# power_board1_v2_0.net
KiCad netlist of a schematic drawn in EAGLE
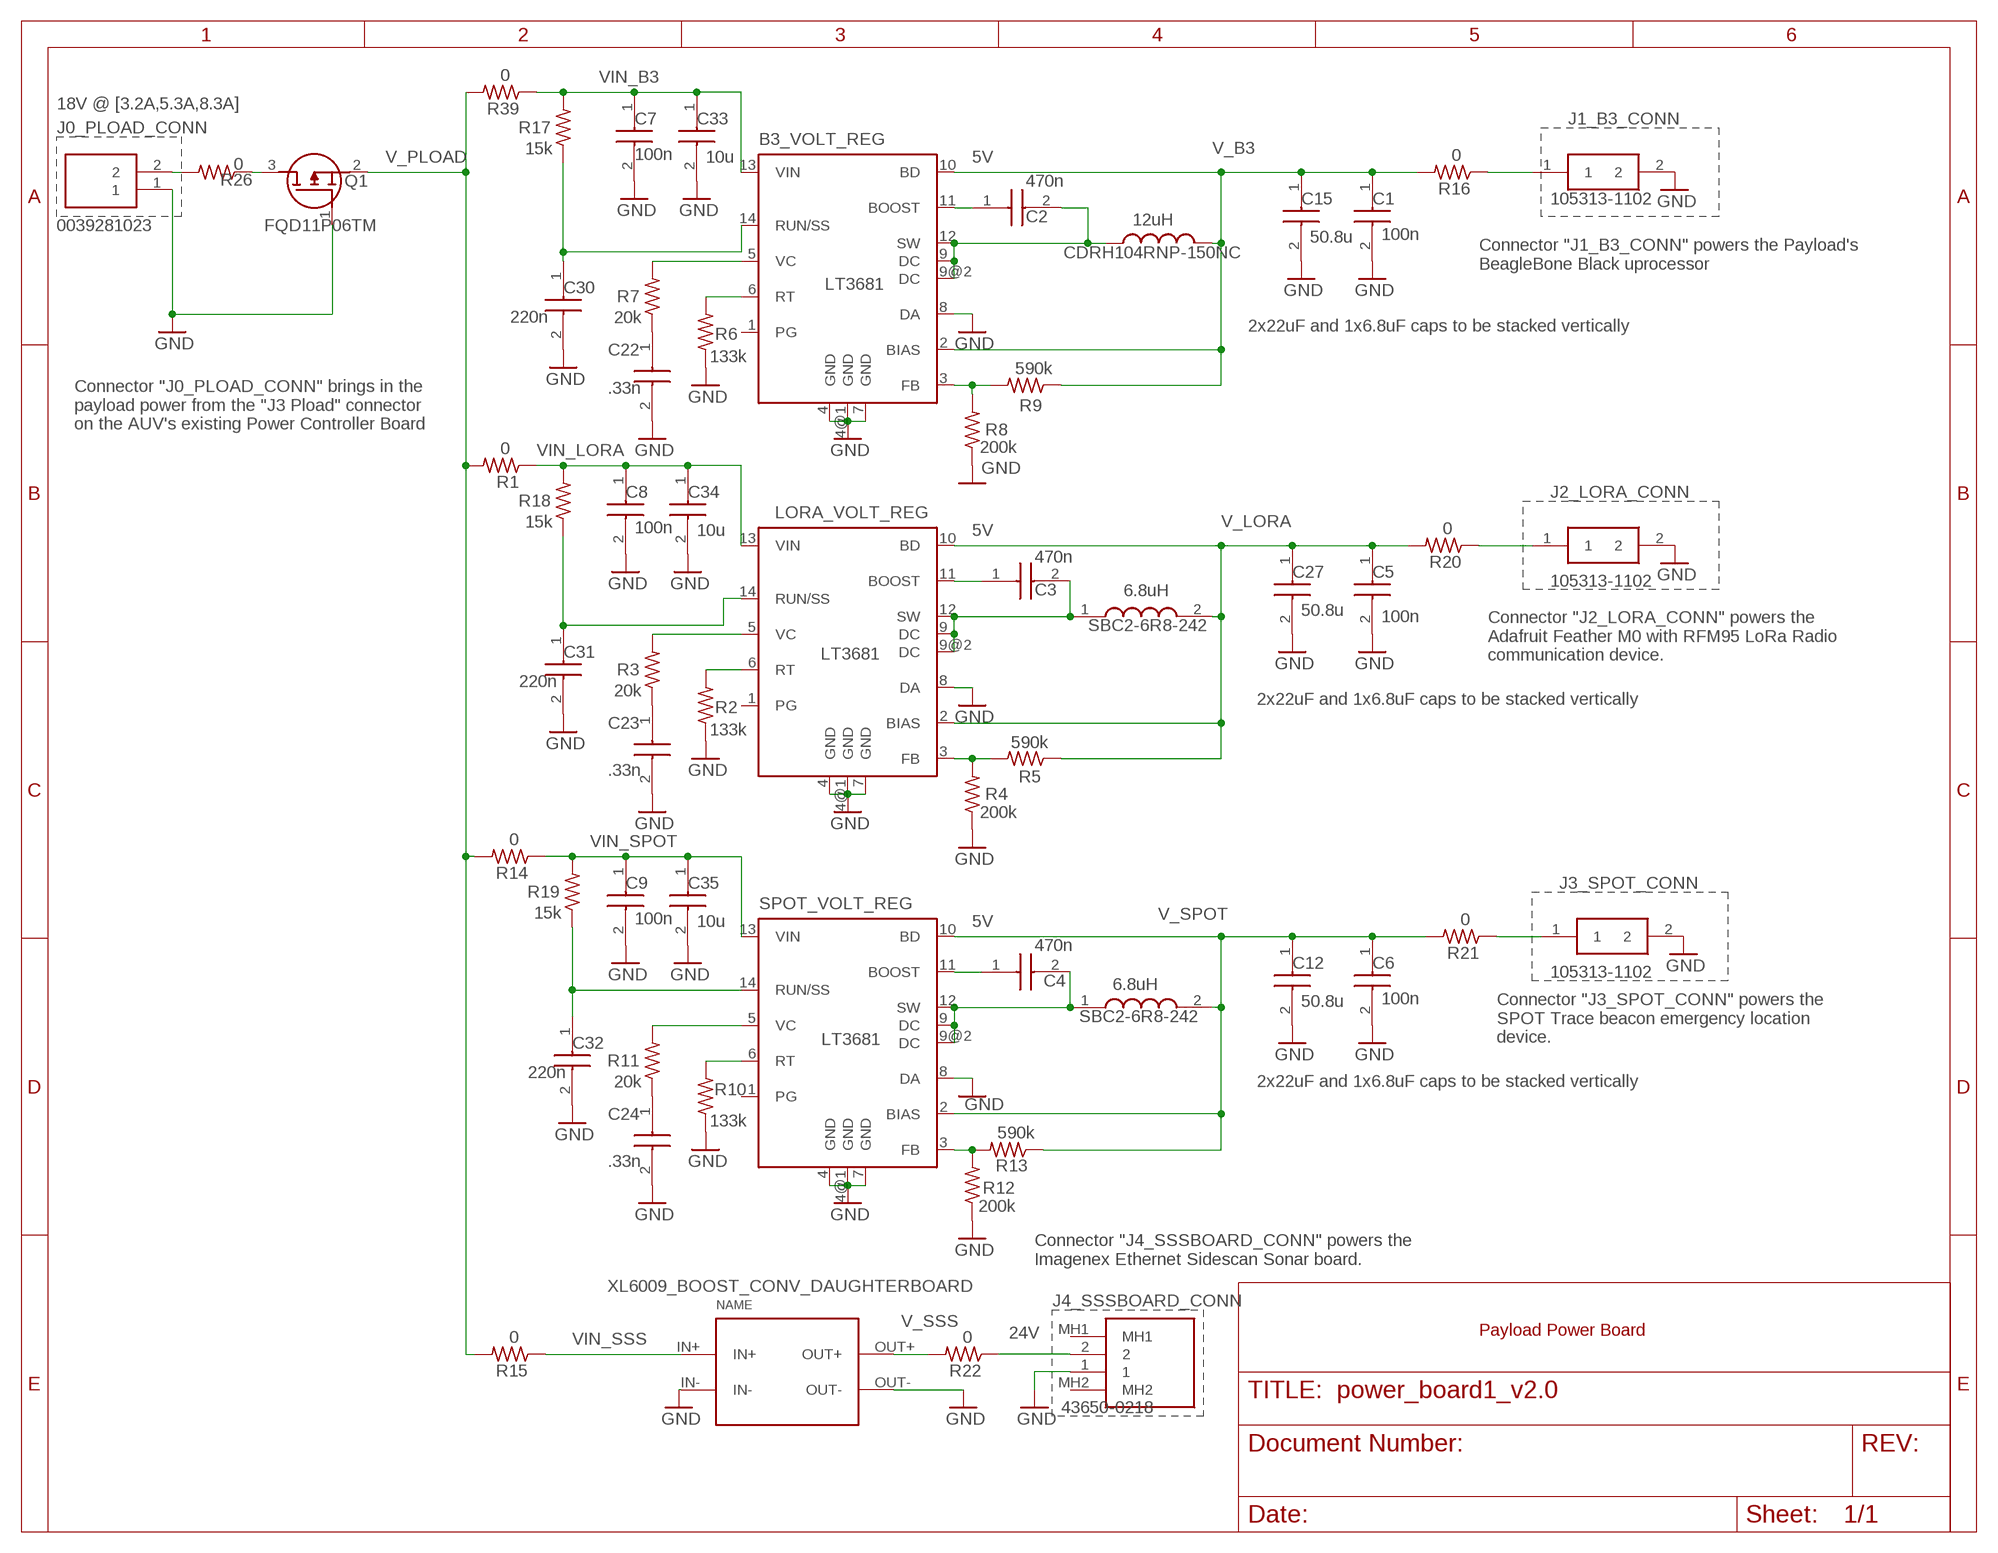
[diagram p0: schematic, sheet 1]

(export (version "E")
  (design (tool "Eeschema 10.0.6"))
  (components
    (comp (ref "B3_VOLT_REG")
      (value "LT3681")
      (footprint "eagle-import:DFN14-4X3DE")
      (fields (field (name "MPN") "LT3681EDE#PBF"))
      (libsource (lib "eagle-import") (part "LT3681"))
    )
    (comp (ref "C1")
      (value "100n")
      (footprint "eagle-import:CAPC1608X90N")
      (fields
        (field (name "MANUFACTURER_PART_NUMBER") "06033C104KAT4A")
        (field (name "MOUSER_PART_NUMBER") "581-06033C104KAT4A")
      )
      (libsource (lib "eagle-import") (part "06033C104KAT4A"))
    )
    (comp (ref "C2")
      (value "470n")
      (footprint "eagle-import:CAPC1608X90N")
      (fields
        (field (name "MANUFACTURER_PART_NUMBER") "06033C474JAT2A")
        (field (name "MOUSER_PART_NUMBER") "581-06033C474JAT2A")
      )
      (libsource (lib "eagle-import") (part "06033C474JAT2A"))
    )
    (comp (ref "C3")
      (value "470n")
      (footprint "eagle-import:CAPC1608X90N")
      (fields
        (field (name "MANUFACTURER_PART_NUMBER") "06033C474JAT2A")
        (field (name "MOUSER_PART_NUMBER") "581-06033C474JAT2A")
      )
      (libsource (lib "eagle-import") (part "06033C474JAT2A"))
    )
    (comp (ref "C4")
      (value "470n")
      (footprint "eagle-import:CAPC1608X90N")
      (fields
        (field (name "MANUFACTURER_PART_NUMBER") "06033C474JAT2A")
        (field (name "MOUSER_PART_NUMBER") "581-06033C474JAT2A")
      )
      (libsource (lib "eagle-import") (part "06033C474JAT2A"))
    )
    (comp (ref "C5")
      (value "100n")
      (footprint "eagle-import:CAPC1608X90N")
      (fields
        (field (name "MANUFACTURER_PART_NUMBER") "06033C104KAT4A")
        (field (name "MOUSER_PART_NUMBER") "581-06033C104KAT4A")
      )
      (libsource (lib "eagle-import") (part "06033C104KAT4A"))
    )
    (comp (ref "C6")
      (value "100n")
      (footprint "eagle-import:CAPC1608X90N")
      (fields
        (field (name "MANUFACTURER_PART_NUMBER") "06033C104KAT4A")
        (field (name "MOUSER_PART_NUMBER") "581-06033C104KAT4A")
      )
      (libsource (lib "eagle-import") (part "06033C104KAT4A"))
    )
    (comp (ref "C7")
      (value "100n")
      (footprint "eagle-import:CAPC1608X90N")
      (fields
        (field (name "MANUFACTURER_PART_NUMBER") "06031C104KAT2A")
        (field (name "MOUSER_PART_NUMBER") "581-06031C104KAT2A")
      )
      (libsource (lib "eagle-import") (part "06031C104KAT2A"))
    )
    (comp (ref "C8")
      (value "100n")
      (footprint "eagle-import:CAPC1608X90N")
      (fields
        (field (name "MANUFACTURER_PART_NUMBER") "06031C104KAT2A")
        (field (name "MOUSER_PART_NUMBER") "581-06031C104KAT2A")
      )
      (libsource (lib "eagle-import") (part "06031C104KAT2A"))
    )
    (comp (ref "C9")
      (value "100n")
      (footprint "eagle-import:CAPC1608X90N")
      (fields
        (field (name "MANUFACTURER_PART_NUMBER") "06031C104KAT2A")
        (field (name "MOUSER_PART_NUMBER") "581-06031C104KAT2A")
      )
      (libsource (lib "eagle-import") (part "06031C104KAT2A"))
    )
    (comp (ref "C12")
      (value "50.8u")
      (footprint "eagle-import:CAPC3225X279N")
      (fields
        (field (name "MANUFACTURER_PART_NUMBER") "12103C226KAT2A")
        (field (name "MOUSER_PART_NUMBER") "581-12103C226KAT2A")
      )
      (libsource (lib "eagle-import") (part "12103C226KAT2A"))
    )
    (comp (ref "C15")
      (value "50.8u")
      (footprint "eagle-import:CAPC3225X279N")
      (fields
        (field (name "MANUFACTURER_PART_NUMBER") "12103C226KAT2A")
        (field (name "MOUSER_PART_NUMBER") "581-12103C226KAT2A")
      )
      (libsource (lib "eagle-import") (part "12103C226KAT2A"))
    )
    (comp (ref "C22")
      (value ".33n")
      (footprint "eagle-import:CAPC2012X140N")
      (fields
        (field (name "MANUFACTURER_PART_NUMBER") "08053C334KAT2A")
        (field (name "MOUSER_PART_NUMBER") "581-08053C334KAT2A")
        (field (name "RS_PART_NUMBER") "1747387")
      )
      (libsource (lib "eagle-import") (part "08053C334KAT2A"))
    )
    (comp (ref "C23")
      (value ".33n")
      (footprint "eagle-import:CAPC2012X140N")
      (fields
        (field (name "MANUFACTURER_PART_NUMBER") "08053C334KAT2A")
        (field (name "MOUSER_PART_NUMBER") "581-08053C334KAT2A")
        (field (name "RS_PART_NUMBER") "1747387")
      )
      (libsource (lib "eagle-import") (part "08053C334KAT2A"))
    )
    (comp (ref "C24")
      (value ".33n")
      (footprint "eagle-import:CAPC2012X140N")
      (fields
        (field (name "MANUFACTURER_PART_NUMBER") "08053C334KAT2A")
        (field (name "MOUSER_PART_NUMBER") "581-08053C334KAT2A")
        (field (name "RS_PART_NUMBER") "1747387")
      )
      (libsource (lib "eagle-import") (part "08053C334KAT2A"))
    )
    (comp (ref "C27")
      (value "50.8u")
      (footprint "eagle-import:CAPC3225X279N")
      (fields
        (field (name "MANUFACTURER_PART_NUMBER") "12103C226KAT2A")
        (field (name "MOUSER_PART_NUMBER") "581-12103C226KAT2A")
      )
      (libsource (lib "eagle-import") (part "12103C226KAT2A"))
    )
    (comp (ref "C30")
      (value "220n")
      (footprint "eagle-import:CAPC2012X140N")
      (fields
        (field (name "MANUFACTURER_PART_NUMBER") "08051C224KAT2A")
        (field (name "MOUSER_PART_NUMBER") "581-08051C224KAT2A")
      )
      (libsource (lib "eagle-import") (part "08051C224KAT2A"))
    )
    (comp (ref "C31")
      (value "220n")
      (footprint "eagle-import:CAPC2012X140N")
      (fields
        (field (name "MANUFACTURER_PART_NUMBER") "08051C224KAT2A")
        (field (name "MOUSER_PART_NUMBER") "581-08051C224KAT2A")
      )
      (libsource (lib "eagle-import") (part "08051C224KAT2A"))
    )
    (comp (ref "C32")
      (value "220n")
      (footprint "eagle-import:CAPC2012X140N")
      (fields
        (field (name "MANUFACTURER_PART_NUMBER") "08051C224KAT2A")
        (field (name "MOUSER_PART_NUMBER") "581-08051C224KAT2A")
      )
      (libsource (lib "eagle-import") (part "08051C224KAT2A"))
    )
    (comp (ref "C33")
      (value "10u")
      (footprint "eagle-import:CAPC5750X279N")
      (fields
        (field (name "MANUFACTURER_PART_NUMBER") "22201C106KAT2A")
        (field (name "MOUSER_PART_NUMBER") "581-22201C106KAT2A")
      )
      (libsource (lib "eagle-import") (part "22201C106KAT2A"))
    )
    (comp (ref "C34")
      (value "10u")
      (footprint "eagle-import:CAPC5750X279N")
      (fields
        (field (name "MANUFACTURER_PART_NUMBER") "22201C106KAT2A")
        (field (name "MOUSER_PART_NUMBER") "581-22201C106KAT2A")
      )
      (libsource (lib "eagle-import") (part "22201C106KAT2A"))
    )
    (comp (ref "C35")
      (value "10u")
      (footprint "eagle-import:CAPC5750X279N")
      (fields
        (field (name "MANUFACTURER_PART_NUMBER") "22201C106KAT2A")
        (field (name "MOUSER_PART_NUMBER") "581-22201C106KAT2A")
      )
      (libsource (lib "eagle-import") (part "22201C106KAT2A"))
    )
    (comp (ref "INDUCTOR_3")
      (value "CDRH104RNP-150NC")
      (footprint "eagle-import:INDPM102100X400N")
      (fields (field (name "MOUSER_PART_NUMBER") "851-CDRH104RNP-150NC"))
      (libsource (lib "eagle-import") (part "CDRH104RNP-150NC"))
    )
    (comp (ref "J0_PLOAD_CONN")
      (value "0039281023")
      (footprint "eagle-import:SHDR2W145P0X550_1X2_960X540X13")
      (libsource (lib "eagle-import") (part "0039281023"))
    )
    (comp (ref "J1_B3_CONN")
      (value "105313-1102")
      (footprint "eagle-import:1053131102")
      (fields (field (name "MOUSER_PART_NUMBER") "538-105313-1102") (field (name "RS_PART_NUMBER") "1623686"))
      (libsource (lib "eagle-import") (part "105313-1102"))
    )
    (comp (ref "J2_LORA_CONN")
      (value "105313-1102")
      (footprint "eagle-import:1053131102")
      (fields (field (name "MOUSER_PART_NUMBER") "538-105313-1102") (field (name "RS_PART_NUMBER") "1623686"))
      (libsource (lib "eagle-import") (part "105313-1102"))
    )
    (comp (ref "J3_SPOT_CONN")
      (value "105313-1102")
      (footprint "eagle-import:1053131102")
      (fields (field (name "MOUSER_PART_NUMBER") "538-105313-1102") (field (name "RS_PART_NUMBER") "1623686"))
      (libsource (lib "eagle-import") (part "105313-1102"))
    )
    (comp (ref "J4_SSSBOARD_CONN")
      (value "43650-0218")
      (footprint "eagle-import:436500218")
      (fields (field (name "MOUSER_PART_NUMBER") "538-43650-0218") (field (name "RS_PART_NUMBER") "6704705P"))
      (libsource (lib "eagle-import") (part "43650-0218"))
    )
    (comp (ref "L4")
      (value "SBC2-6R8-242")
      (footprint "eagle-import:SBC26R8242")
      (fields (field (name "MOUSER_PART_NUMBER") "80-SBC2-6R8-242"))
      (libsource (lib "eagle-import") (part "SBC2-6R8-242"))
    )
    (comp (ref "L5")
      (value "SBC2-6R8-242")
      (footprint "eagle-import:SBC26R8242")
      (fields (field (name "MOUSER_PART_NUMBER") "80-SBC2-6R8-242"))
      (libsource (lib "eagle-import") (part "SBC2-6R8-242"))
    )
    (comp (ref "LORA_VOLT_REG")
      (value "LT3681")
      (footprint "eagle-import:DFN14-4X3DE")
      (fields (field (name "MPN") "LT3681EDE#PBF"))
      (libsource (lib "eagle-import") (part "LT3681"))
    )
    (comp (ref "Q1")
      (value "FQD11P06TM")
      (footprint "eagle-import:DPAK3-CASE-369AS")
      (fields (field (name "MOUSER_PART_NUMBER") "512-FQD11P06TM") (field (name "RS_PART_NUMBER") "6710949P"))
      (libsource (lib "eagle-import") (part "FQD11P06TM"))
    )
    (comp (ref "R1")
      (value "0")
      (footprint "eagle-import:0207_2V")
      (fields (field (name "MFR") "Yageo") (field (name "MPN") "RC0805FR-0710KL"))
      (libsource (lib "eagle-import") (part "R-US_0207/2V"))
    )
    (comp (ref "R2")
      (value "133k")
      (footprint "eagle-import:R0603")
      (libsource (lib "eagle-import") (part "R-US_R0603"))
    )
    (comp (ref "R3")
      (value "20k")
      (footprint "eagle-import:R0603")
      (libsource (lib "eagle-import") (part "R-US_R0603"))
    )
    (comp (ref "R4")
      (value "200k")
      (footprint "eagle-import:R0603")
      (libsource (lib "eagle-import") (part "R-US_R0603"))
    )
    (comp (ref "R5")
      (value "590k")
      (footprint "eagle-import:R0603")
      (libsource (lib "eagle-import") (part "R-US_R0603"))
    )
    (comp (ref "R6")
      (value "133k")
      (footprint "eagle-import:R0603")
      (libsource (lib "eagle-import") (part "R-US_R0603"))
    )
    (comp (ref "R7")
      (value "20k")
      (footprint "eagle-import:R0603")
      (libsource (lib "eagle-import") (part "R-US_R0603"))
    )
    (comp (ref "R8")
      (value "200k")
      (footprint "eagle-import:R0603")
      (libsource (lib "eagle-import") (part "R-US_R0603"))
    )
    (comp (ref "R9")
      (value "590k")
      (footprint "eagle-import:R0603")
      (libsource (lib "eagle-import") (part "R-US_R0603"))
    )
    (comp (ref "R10")
      (value "133k")
      (footprint "eagle-import:R0603")
      (libsource (lib "eagle-import") (part "R-US_R0603"))
    )
    (comp (ref "R11")
      (value "20k")
      (footprint "eagle-import:R0603")
      (libsource (lib "eagle-import") (part "R-US_R0603"))
    )
    (comp (ref "R12")
      (value "200k")
      (footprint "eagle-import:R0603")
      (libsource (lib "eagle-import") (part "R-US_R0603"))
    )
    (comp (ref "R13")
      (value "590k")
      (footprint "eagle-import:R0603")
      (libsource (lib "eagle-import") (part "R-US_R0603"))
    )
    (comp (ref "R14")
      (value "0")
      (footprint "eagle-import:0207_2V")
      (fields (field (name "MFR") "Yageo") (field (name "MPN") "RC0805FR-0710KL"))
      (libsource (lib "eagle-import") (part "R-US_0207/2V"))
    )
    (comp (ref "R15")
      (value "0")
      (footprint "eagle-import:0207_2V")
      (fields (field (name "MFR") "Yageo") (field (name "MPN") "RC0805FR-0710KL"))
      (libsource (lib "eagle-import") (part "R-US_0207/2V"))
    )
    (comp (ref "R16")
      (value "0")
      (footprint "eagle-import:0207_2V")
      (fields (field (name "MFR") "Yageo") (field (name "MPN") "RC0805FR-0710KL"))
      (libsource (lib "eagle-import") (part "R-US_0207/2V"))
    )
    (comp (ref "R17")
      (value "15k")
      (footprint "eagle-import:R0603")
      (libsource (lib "eagle-import") (part "R-US_R0603"))
    )
    (comp (ref "R18")
      (value "15k")
      (footprint "eagle-import:R0603")
      (libsource (lib "eagle-import") (part "R-US_R0603"))
    )
    (comp (ref "R19")
      (value "15k")
      (footprint "eagle-import:R0603")
      (libsource (lib "eagle-import") (part "R-US_R0603"))
    )
    (comp (ref "R20")
      (value "0")
      (footprint "eagle-import:0207_2V")
      (fields (field (name "MFR") "Yageo") (field (name "MPN") "RC0805FR-0710KL"))
      (libsource (lib "eagle-import") (part "R-US_0207/2V"))
    )
    (comp (ref "R21")
      (value "0")
      (footprint "eagle-import:0207_2V")
      (fields (field (name "MFR") "Yageo") (field (name "MPN") "RC0805FR-0710KL"))
      (libsource (lib "eagle-import") (part "R-US_0207/2V"))
    )
    (comp (ref "R22")
      (value "0")
      (footprint "eagle-import:0207_2V")
      (fields (field (name "MFR") "Yageo") (field (name "MPN") "RC0805FR-0710KL"))
      (libsource (lib "eagle-import") (part "R-US_0207/2V"))
    )
    (comp (ref "R26")
      (value "0")
      (footprint "eagle-import:0207_2V")
      (fields (field (name "MFR") "Yageo") (field (name "MPN") "RC0805FR-0710KL"))
      (libsource (lib "eagle-import") (part "R-US_0207/2V"))
    )
    (comp (ref "R39")
      (value "0")
      (footprint "eagle-import:0207_2V")
      (fields (field (name "MFR") "Yageo") (field (name "MPN") "RC0805FR-0710KL"))
      (libsource (lib "eagle-import") (part "R-US_0207/2V"))
    )
    (comp (ref "SPOT_VOLT_REG")
      (value "LT3681")
      (footprint "eagle-import:DFN14-4X3DE")
      (fields (field (name "MPN") "LT3681EDE#PBF"))
      (libsource (lib "eagle-import") (part "LT3681"))
    )
    (comp (ref "XL6009_BOOST_CONV_DAUGHTERBOARD")
      (value "XL6009")
      (footprint "eagle-import:CP8-ADJ")
      (libsource (lib "eagle-import") (part "CP8-ADJ"))
    )
  )
  (nets
    (net (code "1") (name "/VIN_B3") (class "Default")
      (node (ref "B3_VOLT_REG") (pin "13") (pinfunction "VIN_13") (pintype "input"))
      (node (ref "C33") (pin "1") (pinfunction "1_1") (pintype "bidirectional"))
      (node (ref "C7") (pin "1") (pinfunction "1_1") (pintype "bidirectional"))
      (node (ref "R17") (pin "2") (pinfunction "2_2") (pintype "passive"))
      (node (ref "R39") (pin "1") (pinfunction "1_1") (pintype "passive"))
    )
    (net (code "2") (name "/VIN_LORA") (class "Default")
      (node (ref "C34") (pin "1") (pinfunction "1_1") (pintype "bidirectional"))
      (node (ref "C8") (pin "1") (pinfunction "1_1") (pintype "bidirectional"))
      (node (ref "LORA_VOLT_REG") (pin "13") (pinfunction "VIN_13") (pintype "input"))
      (node (ref "R1") (pin "1") (pinfunction "1_1") (pintype "passive"))
      (node (ref "R18") (pin "2") (pinfunction "2_2") (pintype "passive"))
    )
    (net (code "3") (name "/VIN_SPOT") (class "Default")
      (node (ref "C35") (pin "1") (pinfunction "1_1") (pintype "bidirectional"))
      (node (ref "C9") (pin "1") (pinfunction "1_1") (pintype "bidirectional"))
      (node (ref "R14") (pin "1") (pinfunction "1_1") (pintype "passive"))
      (node (ref "R19") (pin "2") (pinfunction "2_2") (pintype "passive"))
      (node (ref "SPOT_VOLT_REG") (pin "13") (pinfunction "VIN_13") (pintype "input"))
    )
    (net (code "4") (name "/VIN_SSS") (class "Default")
      (node (ref "R15") (pin "1") (pinfunction "1_1") (pintype "passive"))
      (node (ref "XL6009_BOOST_CONV_DAUGHTERBOARD") (pin "IN+") (pinfunction "IN+_IN+") (pintype "passive"))
    )
    (net (code "5") (name "/V_B3") (class "Default")
      (node (ref "B3_VOLT_REG") (pin "10") (pinfunction "BD_10") (pintype "input"))
      (node (ref "B3_VOLT_REG") (pin "2") (pinfunction "BIAS_2") (pintype "input"))
      (node (ref "C1") (pin "1") (pinfunction "1_1") (pintype "bidirectional"))
      (node (ref "C15") (pin "1") (pinfunction "1_1") (pintype "bidirectional"))
      (node (ref "INDUCTOR_3") (pin "2") (pinfunction "2_2") (pintype "passive"))
      (node (ref "R16") (pin "2") (pinfunction "2_2") (pintype "passive"))
      (node (ref "R9") (pin "1") (pinfunction "1_1") (pintype "passive"))
    )
    (net (code "6") (name "/V_LORA") (class "Default")
      (node (ref "C27") (pin "1") (pinfunction "1_1") (pintype "bidirectional"))
      (node (ref "C5") (pin "1") (pinfunction "1_1") (pintype "bidirectional"))
      (node (ref "L5") (pin "2") (pinfunction "2_2") (pintype "bidirectional"))
      (node (ref "LORA_VOLT_REG") (pin "10") (pinfunction "BD_10") (pintype "input"))
      (node (ref "LORA_VOLT_REG") (pin "2") (pinfunction "BIAS_2") (pintype "input"))
      (node (ref "R20") (pin "2") (pinfunction "2_2") (pintype "passive"))
      (node (ref "R5") (pin "1") (pinfunction "1_1") (pintype "passive"))
    )
    (net (code "7") (name "/V_PLOAD") (class "Default")
      (node (ref "Q1") (pin "2") (pinfunction "S_2") (pintype "bidirectional"))
      (node (ref "R1") (pin "2") (pinfunction "2_2") (pintype "passive"))
      (node (ref "R14") (pin "2") (pinfunction "2_2") (pintype "passive"))
      (node (ref "R15") (pin "2") (pinfunction "2_2") (pintype "passive"))
      (node (ref "R39") (pin "2") (pinfunction "2_2") (pintype "passive"))
    )
    (net (code "8") (name "/V_SPOT") (class "Default")
      (node (ref "C12") (pin "1") (pinfunction "1_1") (pintype "bidirectional"))
      (node (ref "C6") (pin "1") (pinfunction "1_1") (pintype "bidirectional"))
      (node (ref "L4") (pin "2") (pinfunction "2_2") (pintype "bidirectional"))
      (node (ref "R13") (pin "1") (pinfunction "1_1") (pintype "passive"))
      (node (ref "R21") (pin "2") (pinfunction "2_2") (pintype "passive"))
      (node (ref "SPOT_VOLT_REG") (pin "10") (pinfunction "BD_10") (pintype "input"))
      (node (ref "SPOT_VOLT_REG") (pin "2") (pinfunction "BIAS_2") (pintype "input"))
    )
    (net (code "9") (name "/V_SSS") (class "Default")
      (node (ref "R22") (pin "2") (pinfunction "2_2") (pintype "passive"))
      (node (ref "XL6009_BOOST_CONV_DAUGHTERBOARD") (pin "OUT+") (pinfunction "OUT+_OUT+") (pintype "passive"))
    )
    (net (code "10") (name "GND") (class "Default")
      (node (ref "B3_VOLT_REG") (pin "4") (pinfunction "GND_4") (pintype "input"))
      (node (ref "B3_VOLT_REG") (pin "4@1") (pinfunction "GND_4@1") (pintype "input"))
      (node (ref "B3_VOLT_REG") (pin "7") (pinfunction "GND_7") (pintype "input"))
      (node (ref "B3_VOLT_REG") (pin "8") (pinfunction "DA_8") (pintype "passive"))
      (node (ref "C1") (pin "2") (pinfunction "2_2") (pintype "bidirectional"))
      (node (ref "C12") (pin "2") (pinfunction "2_2") (pintype "bidirectional"))
      (node (ref "C15") (pin "2") (pinfunction "2_2") (pintype "bidirectional"))
      (node (ref "C22") (pin "2") (pinfunction "2_2") (pintype "bidirectional"))
      (node (ref "C23") (pin "2") (pinfunction "2_2") (pintype "bidirectional"))
      (node (ref "C24") (pin "2") (pinfunction "2_2") (pintype "bidirectional"))
      (node (ref "C27") (pin "2") (pinfunction "2_2") (pintype "bidirectional"))
      (node (ref "C30") (pin "2") (pinfunction "2_2") (pintype "bidirectional"))
      (node (ref "C31") (pin "2") (pinfunction "2_2") (pintype "bidirectional"))
      (node (ref "C32") (pin "2") (pinfunction "2_2") (pintype "bidirectional"))
      (node (ref "C33") (pin "2") (pinfunction "2_2") (pintype "bidirectional"))
      (node (ref "C34") (pin "2") (pinfunction "2_2") (pintype "bidirectional"))
      (node (ref "C35") (pin "2") (pinfunction "2_2") (pintype "bidirectional"))
      (node (ref "C5") (pin "2") (pinfunction "2_2") (pintype "bidirectional"))
      (node (ref "C6") (pin "2") (pinfunction "2_2") (pintype "bidirectional"))
      (node (ref "C7") (pin "2") (pinfunction "2_2") (pintype "bidirectional"))
      (node (ref "C8") (pin "2") (pinfunction "2_2") (pintype "bidirectional"))
      (node (ref "C9") (pin "2") (pinfunction "2_2") (pintype "bidirectional"))
      (node (ref "J0_PLOAD_CONN") (pin "1") (pinfunction "1_1") (pintype "bidirectional"))
      (node (ref "J1_B3_CONN") (pin "2") (pinfunction "2_2") (pintype "bidirectional"))
      (node (ref "J2_LORA_CONN") (pin "2") (pinfunction "2_2") (pintype "bidirectional"))
      (node (ref "J3_SPOT_CONN") (pin "2") (pinfunction "2_2") (pintype "bidirectional"))
      (node (ref "J4_SSSBOARD_CONN") (pin "1") (pinfunction "1_1") (pintype "bidirectional"))
      (node (ref "LORA_VOLT_REG") (pin "4") (pinfunction "GND_4") (pintype "input"))
      (node (ref "LORA_VOLT_REG") (pin "4@1") (pinfunction "GND_4@1") (pintype "input"))
      (node (ref "LORA_VOLT_REG") (pin "7") (pinfunction "GND_7") (pintype "input"))
      (node (ref "LORA_VOLT_REG") (pin "8") (pinfunction "DA_8") (pintype "passive"))
      (node (ref "Q1") (pin "1") (pinfunction "G_1") (pintype "bidirectional"))
      (node (ref "R10") (pin "1") (pinfunction "1_1") (pintype "passive"))
      (node (ref "R12") (pin "1") (pinfunction "1_1") (pintype "passive"))
      (node (ref "R2") (pin "1") (pinfunction "1_1") (pintype "passive"))
      (node (ref "R4") (pin "1") (pinfunction "1_1") (pintype "passive"))
      (node (ref "R6") (pin "1") (pinfunction "1_1") (pintype "passive"))
      (node (ref "R8") (pin "1") (pinfunction "1_1") (pintype "passive"))
      (node (ref "SPOT_VOLT_REG") (pin "4") (pinfunction "GND_4") (pintype "input"))
      (node (ref "SPOT_VOLT_REG") (pin "4@1") (pinfunction "GND_4@1") (pintype "input"))
      (node (ref "SPOT_VOLT_REG") (pin "7") (pinfunction "GND_7") (pintype "input"))
      (node (ref "SPOT_VOLT_REG") (pin "8") (pinfunction "DA_8") (pintype "passive"))
      (node (ref "XL6009_BOOST_CONV_DAUGHTERBOARD") (pin "IN-") (pinfunction "IN-_IN-") (pintype "passive"))
      (node (ref "XL6009_BOOST_CONV_DAUGHTERBOARD") (pin "OUT-") (pinfunction "OUT-_OUT-") (pintype "passive"))
    )
    (net (code "11") (name "Net-(B3_VOLT_REG-BOOST)") (class "Default")
      (node (ref "B3_VOLT_REG") (pin "11") (pinfunction "BOOST_11") (pintype "output"))
      (node (ref "C2") (pin "1") (pinfunction "1_1") (pintype "bidirectional"))
    )
    (net (code "12") (name "Net-(B3_VOLT_REG-FB)") (class "Default")
      (node (ref "B3_VOLT_REG") (pin "3") (pinfunction "FB_3") (pintype "input"))
      (node (ref "R8") (pin "2") (pinfunction "2_2") (pintype "passive"))
      (node (ref "R9") (pin "2") (pinfunction "2_2") (pintype "passive"))
    )
    (net (code "13") (name "Net-(B3_VOLT_REG-RT)") (class "Default")
      (node (ref "B3_VOLT_REG") (pin "6") (pinfunction "RT_6") (pintype "input"))
      (node (ref "R6") (pin "2") (pinfunction "2_2") (pintype "passive"))
    )
    (net (code "14") (name "Net-(B3_VOLT_REG-RUN{slash}SS)") (class "Default")
      (node (ref "B3_VOLT_REG") (pin "14") (pinfunction "RUN/SS_14") (pintype "input"))
      (node (ref "C30") (pin "1") (pinfunction "1_1") (pintype "bidirectional"))
      (node (ref "R17") (pin "1") (pinfunction "1_1") (pintype "passive"))
    )
    (net (code "15") (name "Net-(B3_VOLT_REG-SW)") (class "Default")
      (node (ref "B3_VOLT_REG") (pin "12") (pinfunction "SW_12") (pintype "output"))
      (node (ref "B3_VOLT_REG") (pin "9") (pinfunction "DC_9") (pintype "passive"))
      (node (ref "B3_VOLT_REG") (pin "9@2") (pinfunction "DC_9@2") (pintype "passive"))
      (node (ref "C2") (pin "2") (pinfunction "2_2") (pintype "bidirectional"))
      (node (ref "INDUCTOR_3") (pin "1") (pinfunction "1_1") (pintype "passive"))
    )
    (net (code "16") (name "Net-(B3_VOLT_REG-VC)") (class "Default")
      (node (ref "B3_VOLT_REG") (pin "5") (pinfunction "VC_5") (pintype "output"))
      (node (ref "R7") (pin "2") (pinfunction "2_2") (pintype "passive"))
    )
    (net (code "17") (name "Net-(C22-Pad1)") (class "Default")
      (node (ref "C22") (pin "1") (pinfunction "1_1") (pintype "bidirectional"))
      (node (ref "R7") (pin "1") (pinfunction "1_1") (pintype "passive"))
    )
    (net (code "18") (name "Net-(C23-Pad1)") (class "Default")
      (node (ref "C23") (pin "1") (pinfunction "1_1") (pintype "bidirectional"))
      (node (ref "R3") (pin "1") (pinfunction "1_1") (pintype "passive"))
    )
    (net (code "19") (name "Net-(C24-Pad1)") (class "Default")
      (node (ref "C24") (pin "1") (pinfunction "1_1") (pintype "bidirectional"))
      (node (ref "R11") (pin "1") (pinfunction "1_1") (pintype "passive"))
    )
    (net (code "20") (name "Net-(J0_PLOAD_CONN-Pad2)") (class "Default")
      (node (ref "J0_PLOAD_CONN") (pin "2") (pinfunction "2_2") (pintype "bidirectional"))
      (node (ref "R26") (pin "2") (pinfunction "2_2") (pintype "passive"))
    )
    (net (code "21") (name "Net-(J1_B3_CONN-Pad1)") (class "Default")
      (node (ref "J1_B3_CONN") (pin "1") (pinfunction "1_1") (pintype "bidirectional"))
      (node (ref "R16") (pin "1") (pinfunction "1_1") (pintype "passive"))
    )
    (net (code "22") (name "Net-(J2_LORA_CONN-Pad1)") (class "Default")
      (node (ref "J2_LORA_CONN") (pin "1") (pinfunction "1_1") (pintype "bidirectional"))
      (node (ref "R20") (pin "1") (pinfunction "1_1") (pintype "passive"))
    )
    (net (code "23") (name "Net-(J3_SPOT_CONN-Pad1)") (class "Default")
      (node (ref "J3_SPOT_CONN") (pin "1") (pinfunction "1_1") (pintype "bidirectional"))
      (node (ref "R21") (pin "1") (pinfunction "1_1") (pintype "passive"))
    )
    (net (code "24") (name "Net-(J4_SSSBOARD_CONN-Pad2)") (class "Default")
      (node (ref "J4_SSSBOARD_CONN") (pin "2") (pinfunction "2_2") (pintype "bidirectional"))
      (node (ref "R22") (pin "1") (pinfunction "1_1") (pintype "passive"))
    )
    (net (code "25") (name "Net-(LORA_VOLT_REG-BOOST)") (class "Default")
      (node (ref "C3") (pin "1") (pinfunction "1_1") (pintype "bidirectional"))
      (node (ref "LORA_VOLT_REG") (pin "11") (pinfunction "BOOST_11") (pintype "output"))
    )
    (net (code "26") (name "Net-(LORA_VOLT_REG-FB)") (class "Default")
      (node (ref "LORA_VOLT_REG") (pin "3") (pinfunction "FB_3") (pintype "input"))
      (node (ref "R4") (pin "2") (pinfunction "2_2") (pintype "passive"))
      (node (ref "R5") (pin "2") (pinfunction "2_2") (pintype "passive"))
    )
    (net (code "27") (name "Net-(LORA_VOLT_REG-RT)") (class "Default")
      (node (ref "LORA_VOLT_REG") (pin "6") (pinfunction "RT_6") (pintype "input"))
      (node (ref "R2") (pin "2") (pinfunction "2_2") (pintype "passive"))
    )
    (net (code "28") (name "Net-(LORA_VOLT_REG-RUN{slash}SS)") (class "Default")
      (node (ref "C31") (pin "1") (pinfunction "1_1") (pintype "bidirectional"))
      (node (ref "LORA_VOLT_REG") (pin "14") (pinfunction "RUN/SS_14") (pintype "input"))
      (node (ref "R18") (pin "1") (pinfunction "1_1") (pintype "passive"))
    )
    (net (code "29") (name "Net-(LORA_VOLT_REG-SW)") (class "Default")
      (node (ref "C3") (pin "2") (pinfunction "2_2") (pintype "bidirectional"))
      (node (ref "L5") (pin "1") (pinfunction "1_1") (pintype "bidirectional"))
      (node (ref "LORA_VOLT_REG") (pin "12") (pinfunction "SW_12") (pintype "output"))
      (node (ref "LORA_VOLT_REG") (pin "9") (pinfunction "DC_9") (pintype "passive"))
      (node (ref "LORA_VOLT_REG") (pin "9@2") (pinfunction "DC_9@2") (pintype "passive"))
    )
    (net (code "30") (name "Net-(LORA_VOLT_REG-VC)") (class "Default")
      (node (ref "LORA_VOLT_REG") (pin "5") (pinfunction "VC_5") (pintype "output"))
      (node (ref "R3") (pin "2") (pinfunction "2_2") (pintype "passive"))
    )
    (net (code "31") (name "Net-(Q1-D)") (class "Default")
      (node (ref "Q1") (pin "3") (pinfunction "D_3") (pintype "bidirectional"))
      (node (ref "R26") (pin "1") (pinfunction "1_1") (pintype "passive"))
    )
    (net (code "32") (name "Net-(SPOT_VOLT_REG-BOOST)") (class "Default")
      (node (ref "C4") (pin "1") (pinfunction "1_1") (pintype "bidirectional"))
      (node (ref "SPOT_VOLT_REG") (pin "11") (pinfunction "BOOST_11") (pintype "output"))
    )
    (net (code "33") (name "Net-(SPOT_VOLT_REG-FB)") (class "Default")
      (node (ref "R12") (pin "2") (pinfunction "2_2") (pintype "passive"))
      (node (ref "R13") (pin "2") (pinfunction "2_2") (pintype "passive"))
      (node (ref "SPOT_VOLT_REG") (pin "3") (pinfunction "FB_3") (pintype "input"))
    )
    (net (code "34") (name "Net-(SPOT_VOLT_REG-RT)") (class "Default")
      (node (ref "R10") (pin "2") (pinfunction "2_2") (pintype "passive"))
      (node (ref "SPOT_VOLT_REG") (pin "6") (pinfunction "RT_6") (pintype "input"))
    )
    (net (code "35") (name "Net-(SPOT_VOLT_REG-RUN{slash}SS)") (class "Default")
      (node (ref "C32") (pin "1") (pinfunction "1_1") (pintype "bidirectional"))
      (node (ref "R19") (pin "1") (pinfunction "1_1") (pintype "passive"))
      (node (ref "SPOT_VOLT_REG") (pin "14") (pinfunction "RUN/SS_14") (pintype "input"))
    )
    (net (code "36") (name "Net-(SPOT_VOLT_REG-SW)") (class "Default")
      (node (ref "C4") (pin "2") (pinfunction "2_2") (pintype "bidirectional"))
      (node (ref "L4") (pin "1") (pinfunction "1_1") (pintype "bidirectional"))
      (node (ref "SPOT_VOLT_REG") (pin "12") (pinfunction "SW_12") (pintype "output"))
      (node (ref "SPOT_VOLT_REG") (pin "9") (pinfunction "DC_9") (pintype "passive"))
      (node (ref "SPOT_VOLT_REG") (pin "9@2") (pinfunction "DC_9@2") (pintype "passive"))
    )
    (net (code "37") (name "Net-(SPOT_VOLT_REG-VC)") (class "Default")
      (node (ref "R11") (pin "2") (pinfunction "2_2") (pintype "passive"))
      (node (ref "SPOT_VOLT_REG") (pin "5") (pinfunction "VC_5") (pintype "output"))
    )
    (net (code "38") (name "unconnected-(B3_VOLT_REG-PG-Pad1)") (class "Default")
      (node (ref "B3_VOLT_REG") (pin "1") (pinfunction "PG_1") (pintype "open_collector"))
    )
    (net (code "39") (name "unconnected-(J4_SSSBOARD_CONN-PadMH1)") (class "Default")
      (node (ref "J4_SSSBOARD_CONN") (pin "MH1") (pinfunction "MH1_MH1") (pintype "bidirectional"))
    )
    (net (code "40") (name "unconnected-(J4_SSSBOARD_CONN-PadMH2)") (class "Default")
      (node (ref "J4_SSSBOARD_CONN") (pin "MH2") (pinfunction "MH2_MH2") (pintype "bidirectional"))
    )
    (net (code "41") (name "unconnected-(LORA_VOLT_REG-PG-Pad1)") (class "Default")
      (node (ref "LORA_VOLT_REG") (pin "1") (pinfunction "PG_1") (pintype "open_collector"))
    )
    (net (code "42") (name "unconnected-(SPOT_VOLT_REG-PG-Pad1)") (class "Default")
      (node (ref "SPOT_VOLT_REG") (pin "1") (pinfunction "PG_1") (pintype "open_collector"))
    )
  )
)
